# bb-psu-mk-1_1.net
KiCad netlist of a schematic drawn in EAGLE
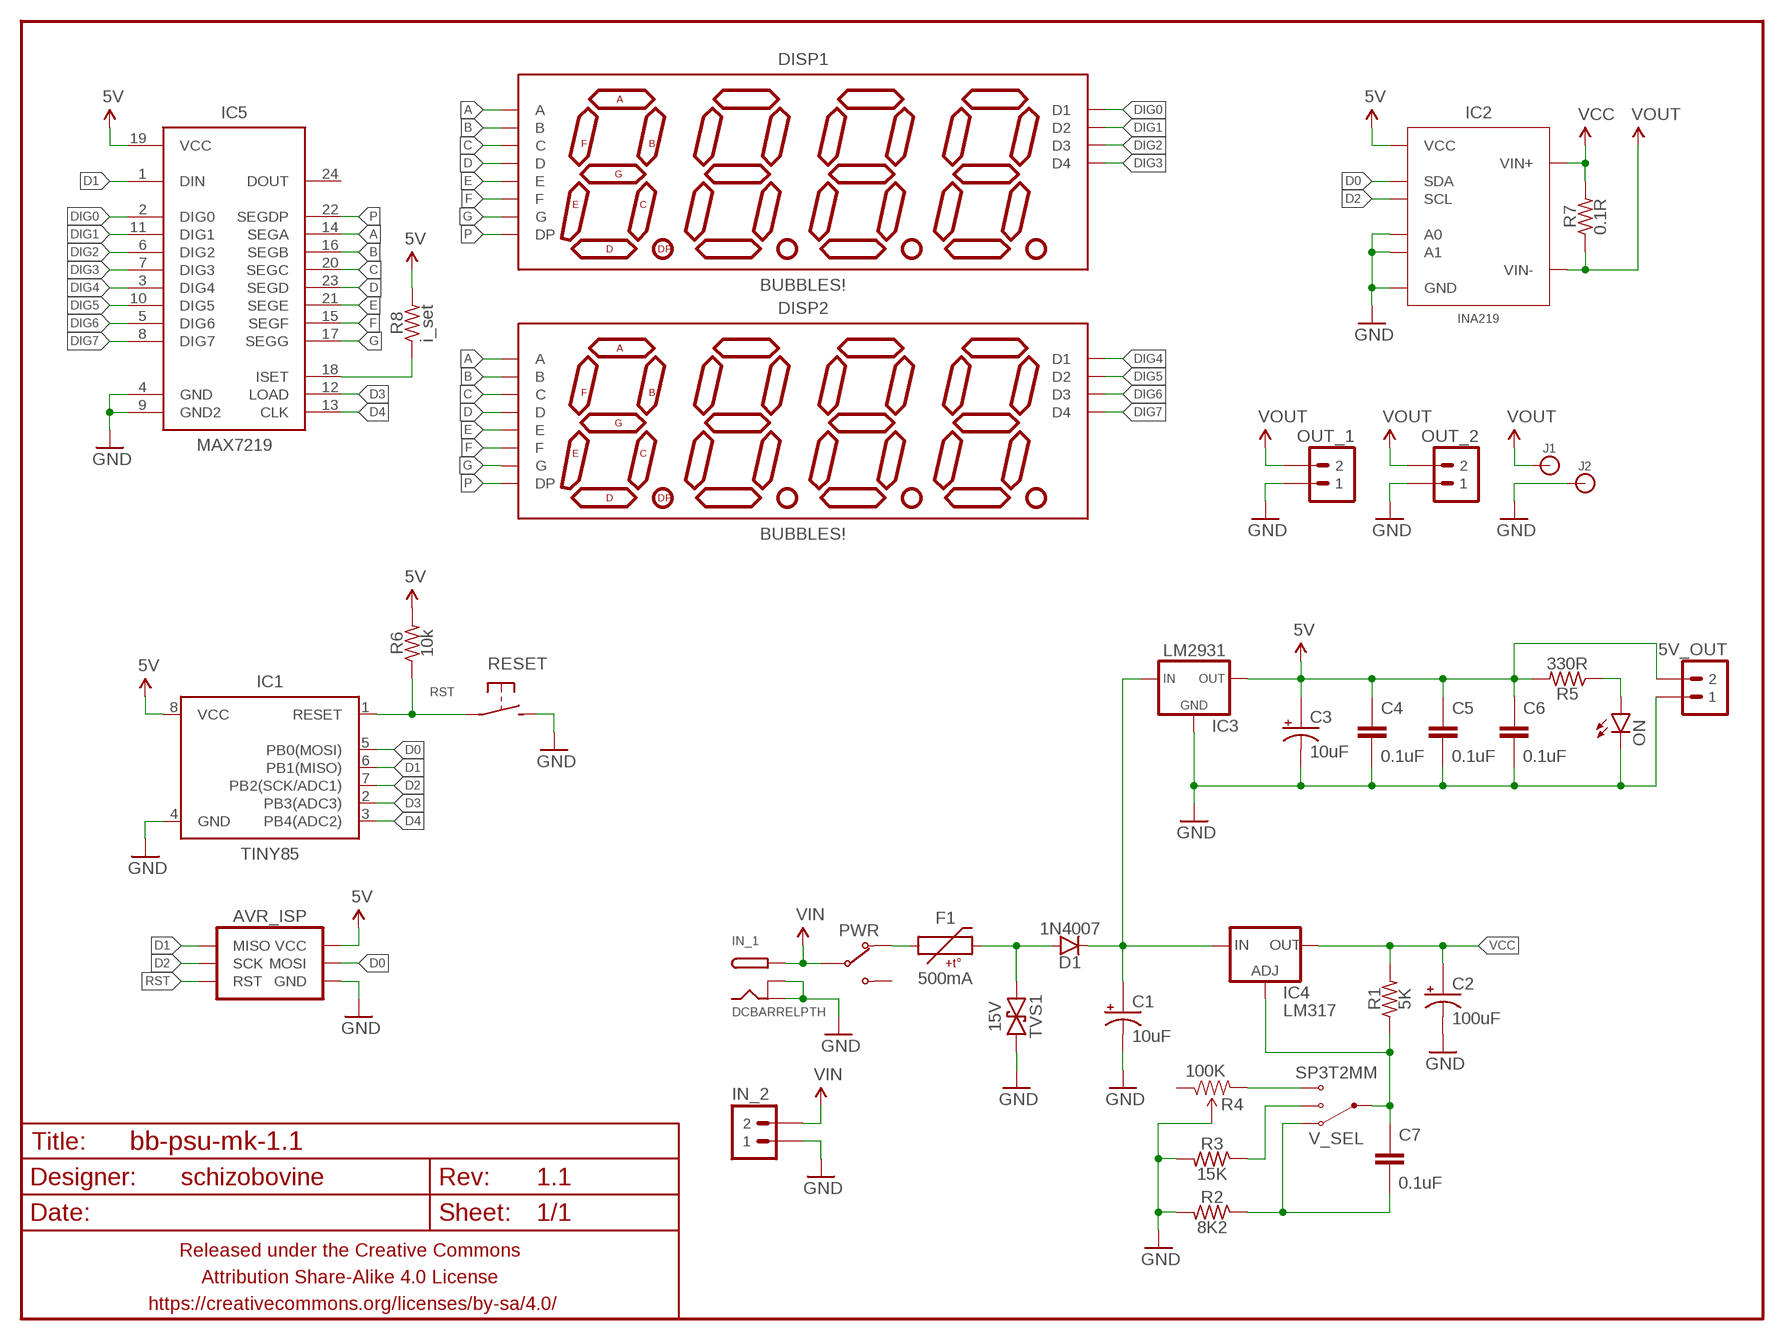
[diagram p0: schematic, sheet 1]

(export (version "E")
  (design (tool "Eeschema 10.0.6"))
  (components
    (comp (ref "5V_OUT")
      (value "M02PTH-CENTERED-R+")
      (footprint "eagle-import:1X02-CENTER-R+")
      (libsource (lib "eagle-import") (part "M02PTH-CENTERED-R+"))
    )
    (comp (ref "AVR_ISP")
      (value "AVR_SPI_PRG_6PTH")
      (footprint "eagle-import:2X3")
      (libsource (lib "eagle-import") (part "AVR_SPI_PRG_6PTH"))
    )
    (comp (ref "C1")
      (value "10uF")
      (footprint "eagle-import:E2,5-6")
      (libsource (lib "eagle-import") (part "CAPACITOR-POLARIZEDE2.5-6"))
    )
    (comp (ref "C2")
      (value "100uF")
      (footprint "eagle-import:E2,5-6")
      (libsource (lib "eagle-import") (part "CAPACITOR-POLARIZEDE2.5-6"))
    )
    (comp (ref "C3")
      (value "10uF")
      (footprint "eagle-import:E2-5")
      (libsource (lib "eagle-import") (part "CAPACITOR-POLARIZEDE2-5"))
    )
    (comp (ref "C4")
      (value "0.1uF")
      (footprint "eagle-import:C025-024X044")
      (libsource (lib "eagle-import") (part "CAPACITOR-CERAMIC025-024X044"))
    )
    (comp (ref "C5")
      (value "0.1uF")
      (footprint "eagle-import:C025-024X044")
      (libsource (lib "eagle-import") (part "CAPACITOR-CERAMIC025-024X044"))
    )
    (comp (ref "C6")
      (value "0.1uF")
      (footprint "eagle-import:C025-024X044")
      (libsource (lib "eagle-import") (part "CAPACITOR-CERAMIC025-024X044"))
    )
    (comp (ref "C7")
      (value "0.1uF")
      (footprint "eagle-import:C025-024X044")
      (libsource (lib "eagle-import") (part "CAPACITOR-CERAMIC025-024X044"))
    )
    (comp (ref "D1")
      (value "1N4007")
      (footprint "eagle-import:DIODE-10.16MM")
      (libsource (lib "eagle-import") (part "DIODEPTH-10.68MM"))
    )
    (comp (ref "DISP1")
      (value "BUBBLES!")
      (footprint "eagle-import:DIL12")
      (libsource (lib "eagle-import") (part "7SEG_4DIGITHP-BUBBLE"))
    )
    (comp (ref "DISP2")
      (value "BUBBLES!")
      (footprint "eagle-import:DIL12")
      (libsource (lib "eagle-import") (part "7SEG_4DIGITHP-BUBBLE"))
    )
    (comp (ref "F1")
      (value "500mA")
      (footprint "eagle-import:PTC-PTH-5.08MM")
      (libsource (lib "eagle-import") (part "PTCPTH-5.08MM"))
    )
    (comp (ref "FRAME1")
      (value "FRAME-LETTERNO_PACKAGE")
      (footprint "eagle-import:DUMMY")
      (fields (field (name "DESIGNER") "schizobovine") (field (name "VERSION") "1.1"))
      (libsource (lib "eagle-import") (part "FRAME-LETTERNO_PACKAGE"))
    )
    (comp (ref "IC1")
      (value "TINY85")
      (footprint "eagle-import:DIP08")
      (libsource (lib "eagle-import") (part "ATTINY45TINY85-20-DIP"))
    )
    (comp (ref "IC2")
      (value "INA219")
      (footprint "eagle-import:SO08")
      (libsource (lib "eagle-import") (part "INA219SOIC8"))
    )
    (comp (ref "IC3")
      (value "LM2931")
      (footprint "eagle-import:TO-92-AMMO")
      (libsource (lib "eagle-import") (part "V_REG_78XXTO-92-INLINE"))
    )
    (comp (ref "IC4")
      (value "LM317")
      (footprint "eagle-import:TO220-THERMPAD")
      (libsource (lib "eagle-import") (part "V_REG_317THERMPAD"))
    )
    (comp (ref "IC5")
      (value "MAX7219")
      (footprint "eagle-import:SO24W")
      (libsource (lib "eagle-import") (part "MAX7219SOIC-W"))
    )
    (comp (ref "IN_1")
      (value "DCBARRELPTH")
      (footprint "eagle-import:DCJACK_2MM_PTH")
      (libsource (lib "eagle-import") (part "DCBARRELPTH"))
    )
    (comp (ref "IN_2")
      (value "M02PTH-CENTERED-R+")
      (footprint "eagle-import:1X02-CENTER-R+")
      (libsource (lib "eagle-import") (part "M02PTH-CENTERED-R+"))
    )
    (comp (ref "J1")
      (value "BANANA_CONNPOAST")
      (footprint "eagle-import:BINDING_POST")
      (libsource (lib "eagle-import") (part "BANANA_CONNPOAST"))
    )
    (comp (ref "J2")
      (value "BANANA_CONNPOAST")
      (footprint "eagle-import:BINDING_POST")
      (libsource (lib "eagle-import") (part "BANANA_CONNPOAST"))
    )
    (comp (ref "ON")
      (value "LED3MM-LESS")
      (footprint "eagle-import:LED3MM-LESSSILK")
      (libsource (lib "eagle-import") (part "LED3MM-LESS"))
    )
    (comp (ref "OUT_1")
      (value "M02PTH-CENTERED-R+")
      (footprint "eagle-import:1X02-CENTER-R+")
      (libsource (lib "eagle-import") (part "M02PTH-CENTERED-R+"))
    )
    (comp (ref "OUT_2")
      (value "M02PTH-CENTERED-R+")
      (footprint "eagle-import:1X02-CENTER-R+")
      (libsource (lib "eagle-import") (part "M02PTH-CENTERED-R+"))
    )
    (comp (ref "PWR")
      (value "SWITCH-SPDTPTH-VERT-2.54MM")
      (footprint "eagle-import:SWITCH-SPDT")
      (libsource (lib "eagle-import") (part "SWITCH-SPDTPTH-VERT-2.54MM"))
    )
    (comp (ref "R1")
      (value "5K")
      (footprint "eagle-import:RESISTOR-AXIAL-PTH-6.35MM")
      (libsource (lib "eagle-import") (part "RESISTORPTH-AXIAL-6.35MM"))
    )
    (comp (ref "R2")
      (value "8K2")
      (footprint "eagle-import:RESISTOR-AXIAL-PTH-6.35MM")
      (libsource (lib "eagle-import") (part "RESISTORPTH-AXIAL-6.35MM"))
    )
    (comp (ref "R3")
      (value "15K")
      (footprint "eagle-import:RESISTOR-AXIAL-PTH-6.35MM")
      (libsource (lib "eagle-import") (part "RESISTORPTH-AXIAL-6.35MM"))
    )
    (comp (ref "R4")
      (value "100K")
      (footprint "eagle-import:3386U")
      (libsource (lib "eagle-import") (part "TRIMPOT-PTH-KNOB"))
    )
    (comp (ref "R5")
      (value "330R")
      (footprint "eagle-import:RESISTOR-AXIAL-PTH-5.08MM")
      (libsource (lib "eagle-import") (part "RESISTORPTH-AXIAL-5.08MM"))
    )
    (comp (ref "R6")
      (value "10k")
      (footprint "eagle-import:RESISTOR-AXIAL-PTH-5.08MM")
      (libsource (lib "eagle-import") (part "RESISTORPTH-AXIAL-5.08MM"))
    )
    (comp (ref "R7")
      (value "0.1R")
      (footprint "eagle-import:RESISTOR-AXIAL-PTH-10.16MM")
      (libsource (lib "eagle-import") (part "RESISTORPTH-AXIAL-10.16MM"))
    )
    (comp (ref "R8")
      (value "i_set")
      (footprint "eagle-import:RESISTOR-AXIAL-PTH-5.08MM")
      (libsource (lib "eagle-import") (part "RESISTORPTH-AXIAL-5.08MM"))
    )
    (comp (ref "RESET")
      (value "SPST-NO-TACT3MM-PTH-SMALL-PADS")
      (footprint "eagle-import:DTS-3-SMALL-PADS")
      (libsource (lib "eagle-import") (part "SPST-NO-TACT3MM-PTH-SMALL-PADS"))
    )
    (comp (ref "TVS1")
      (value "15V")
      (footprint "eagle-import:DO-41-TVS-BI-10.16MM")
      (libsource (lib "eagle-import") (part "TVSDO-41-10.16MM"))
    )
    (comp (ref "V_SEL")
      (value "SP3T2MM")
      (footprint "eagle-import:SP3T-2MM")
      (libsource (lib "eagle-import") (part "SP3T2MM"))
    )
  )
  (nets
    (net (code "1") (name "5V") (class "Default")
      (node (ref "5V_OUT") (pin "2") (pinfunction "2_2") (pintype "passive"))
      (node (ref "AVR_ISP") (pin "2") (pinfunction "VCC_2") (pintype "passive"))
      (node (ref "C3") (pin "+") (pinfunction "+_+") (pintype "passive"))
      (node (ref "C4") (pin "1") (pinfunction "1_1") (pintype "passive"))
      (node (ref "C5") (pin "1") (pinfunction "1_1") (pintype "passive"))
      (node (ref "C6") (pin "1") (pinfunction "1_1") (pintype "passive"))
      (node (ref "IC1") (pin "8") (pinfunction "VCC_8") (pintype "bidirectional"))
      (node (ref "IC2") (pin "5") (pinfunction "VCC_5") (pintype "bidirectional"))
      (node (ref "IC3") (pin "3") (pinfunction "OUT_3") (pintype "bidirectional"))
      (node (ref "IC5") (pin "19") (pinfunction "VCC_19") (pintype "bidirectional"))
      (node (ref "R5") (pin "P$2") (pinfunction "2_P$2") (pintype "passive"))
      (node (ref "R6") (pin "P$2") (pinfunction "2_P$2") (pintype "passive"))
      (node (ref "R8") (pin "P$2") (pinfunction "2_P$2") (pintype "passive"))
    )
    (net (code "2") (name "A") (class "Default")
      (node (ref "DISP1") (pin "12") (pinfunction "A_12") (pintype "bidirectional"))
      (node (ref "DISP2") (pin "12") (pinfunction "A_12") (pintype "bidirectional"))
      (node (ref "IC5") (pin "14") (pinfunction "SEGA_14") (pintype "bidirectional"))
    )
    (net (code "3") (name "B") (class "Default")
      (node (ref "DISP1") (pin "11") (pinfunction "B_11") (pintype "bidirectional"))
      (node (ref "DISP2") (pin "11") (pinfunction "B_11") (pintype "bidirectional"))
      (node (ref "IC5") (pin "16") (pinfunction "SEGB_16") (pintype "bidirectional"))
    )
    (net (code "4") (name "C") (class "Default")
      (node (ref "DISP1") (pin "3") (pinfunction "C_3") (pintype "bidirectional"))
      (node (ref "DISP2") (pin "3") (pinfunction "C_3") (pintype "bidirectional"))
      (node (ref "IC5") (pin "20") (pinfunction "SEGC_20") (pintype "bidirectional"))
    )
    (net (code "5") (name "D") (class "Default")
      (node (ref "DISP1") (pin "8") (pinfunction "D_8") (pintype "bidirectional"))
      (node (ref "DISP2") (pin "8") (pinfunction "D_8") (pintype "bidirectional"))
      (node (ref "IC5") (pin "23") (pinfunction "SEGD_23") (pintype "bidirectional"))
    )
    (net (code "6") (name "D0") (class "Default")
      (node (ref "AVR_ISP") (pin "4") (pinfunction "MOSI_4") (pintype "passive"))
      (node (ref "IC1") (pin "5") (pinfunction "PB0(MOSI)_5") (pintype "bidirectional"))
      (node (ref "IC2") (pin "3") (pinfunction "SDA_3") (pintype "bidirectional"))
    )
    (net (code "7") (name "D1") (class "Default")
      (node (ref "AVR_ISP") (pin "1") (pinfunction "MISO_1") (pintype "passive"))
      (node (ref "IC1") (pin "6") (pinfunction "PB1(MISO)_6") (pintype "bidirectional"))
      (node (ref "IC5") (pin "1") (pinfunction "DIN_1") (pintype "bidirectional"))
    )
    (net (code "8") (name "D2") (class "Default")
      (node (ref "AVR_ISP") (pin "3") (pinfunction "SCK_3") (pintype "passive"))
      (node (ref "IC1") (pin "7") (pinfunction "PB2(SCK/ADC1)_7") (pintype "bidirectional"))
      (node (ref "IC2") (pin "4") (pinfunction "SCL_4") (pintype "bidirectional"))
    )
    (net (code "9") (name "D3") (class "Default")
      (node (ref "IC1") (pin "2") (pinfunction "PB3(ADC3)_2") (pintype "bidirectional"))
      (node (ref "IC5") (pin "12") (pinfunction "LOAD_12") (pintype "bidirectional"))
    )
    (net (code "10") (name "D4") (class "Default")
      (node (ref "IC1") (pin "3") (pinfunction "PB4(ADC2)_3") (pintype "bidirectional"))
      (node (ref "IC5") (pin "13") (pinfunction "CLK_13") (pintype "bidirectional"))
    )
    (net (code "11") (name "DIG0") (class "Default")
      (node (ref "DISP1") (pin "1") (pinfunction "D1_1") (pintype "bidirectional"))
      (node (ref "IC5") (pin "2") (pinfunction "DIG0_2") (pintype "bidirectional"))
    )
    (net (code "12") (name "DIG1") (class "Default")
      (node (ref "DISP1") (pin "10") (pinfunction "D2_10") (pintype "bidirectional"))
      (node (ref "IC5") (pin "11") (pinfunction "DIG1_11") (pintype "bidirectional"))
    )
    (net (code "13") (name "DIG2") (class "Default")
      (node (ref "DISP1") (pin "4") (pinfunction "D3_4") (pintype "bidirectional"))
      (node (ref "IC5") (pin "6") (pinfunction "DIG2_6") (pintype "bidirectional"))
    )
    (net (code "14") (name "DIG3") (class "Default")
      (node (ref "DISP1") (pin "6") (pinfunction "D4_6") (pintype "bidirectional"))
      (node (ref "IC5") (pin "7") (pinfunction "DIG3_7") (pintype "bidirectional"))
    )
    (net (code "15") (name "DIG4") (class "Default")
      (node (ref "DISP2") (pin "1") (pinfunction "D1_1") (pintype "bidirectional"))
      (node (ref "IC5") (pin "3") (pinfunction "DIG4_3") (pintype "bidirectional"))
    )
    (net (code "16") (name "DIG5") (class "Default")
      (node (ref "DISP2") (pin "10") (pinfunction "D2_10") (pintype "bidirectional"))
      (node (ref "IC5") (pin "10") (pinfunction "DIG5_10") (pintype "bidirectional"))
    )
    (net (code "17") (name "DIG6") (class "Default")
      (node (ref "DISP2") (pin "4") (pinfunction "D3_4") (pintype "bidirectional"))
      (node (ref "IC5") (pin "5") (pinfunction "DIG6_5") (pintype "bidirectional"))
    )
    (net (code "18") (name "DIG7") (class "Default")
      (node (ref "DISP2") (pin "6") (pinfunction "D4_6") (pintype "bidirectional"))
      (node (ref "IC5") (pin "8") (pinfunction "DIG7_8") (pintype "bidirectional"))
    )
    (net (code "19") (name "E") (class "Default")
      (node (ref "DISP1") (pin "2") (pinfunction "E_2") (pintype "bidirectional"))
      (node (ref "DISP2") (pin "2") (pinfunction "E_2") (pintype "bidirectional"))
      (node (ref "IC5") (pin "21") (pinfunction "SEGE_21") (pintype "bidirectional"))
    )
    (net (code "20") (name "F") (class "Default")
      (node (ref "DISP1") (pin "9") (pinfunction "F_9") (pintype "bidirectional"))
      (node (ref "DISP2") (pin "9") (pinfunction "F_9") (pintype "bidirectional"))
      (node (ref "IC5") (pin "15") (pinfunction "SEGF_15") (pintype "bidirectional"))
    )
    (net (code "21") (name "G") (class "Default")
      (node (ref "DISP1") (pin "7") (pinfunction "G_7") (pintype "bidirectional"))
      (node (ref "DISP2") (pin "7") (pinfunction "G_7") (pintype "bidirectional"))
      (node (ref "IC5") (pin "17") (pinfunction "SEGG_17") (pintype "bidirectional"))
    )
    (net (code "22") (name "GND") (class "Default")
      (node (ref "5V_OUT") (pin "1") (pinfunction "1_1") (pintype "passive"))
      (node (ref "AVR_ISP") (pin "6") (pinfunction "GND_6") (pintype "passive"))
      (node (ref "C1") (pin "-") (pinfunction "-_-") (pintype "passive"))
      (node (ref "C2") (pin "-") (pinfunction "-_-") (pintype "passive"))
      (node (ref "C3") (pin "-") (pinfunction "-_-") (pintype "passive"))
      (node (ref "C4") (pin "2") (pinfunction "2_2") (pintype "passive"))
      (node (ref "C5") (pin "2") (pinfunction "2_2") (pintype "passive"))
      (node (ref "C6") (pin "2") (pinfunction "2_2") (pintype "passive"))
      (node (ref "IC1") (pin "4") (pinfunction "GND_4") (pintype "bidirectional"))
      (node (ref "IC2") (pin "1") (pinfunction "A1_1") (pintype "bidirectional"))
      (node (ref "IC2") (pin "2") (pinfunction "A0_2") (pintype "bidirectional"))
      (node (ref "IC2") (pin "6") (pinfunction "GND_6") (pintype "bidirectional"))
      (node (ref "IC3") (pin "2") (pinfunction "GND_2") (pintype "bidirectional"))
      (node (ref "IC5") (pin "4") (pinfunction "GND_4") (pintype "bidirectional"))
      (node (ref "IC5") (pin "9") (pinfunction "GND2_9") (pintype "bidirectional"))
      (node (ref "IN_1") (pin "BRK") (pinfunction "BRK_BRK") (pintype "bidirectional"))
      (node (ref "IN_1") (pin "GND") (pinfunction "GND_GND") (pintype "bidirectional"))
      (node (ref "IN_2") (pin "1") (pinfunction "1_1") (pintype "passive"))
      (node (ref "J2") (pin "P$1") (pinfunction "1_P$1") (pintype "passive"))
      (node (ref "ON") (pin "K") (pinfunction "C_K") (pintype "passive"))
      (node (ref "OUT_1") (pin "1") (pinfunction "1_1") (pintype "passive"))
      (node (ref "OUT_2") (pin "1") (pinfunction "1_1") (pintype "passive"))
      (node (ref "R2") (pin "P$2") (pinfunction "2_P$2") (pintype "passive"))
      (node (ref "R3") (pin "P$2") (pinfunction "2_P$2") (pintype "passive"))
      (node (ref "R4") (pin "2") (pinfunction "WIPER_2") (pintype "passive"))
      (node (ref "RESET") (pin "2") (pinfunction "2_2") (pintype "passive"))
      (node (ref "TVS1") (pin "P$2") (pinfunction "2_P$2") (pintype "passive"))
    )
    (net (code "23") (name "Net-(F1-1)") (class "Default")
      (node (ref "F1") (pin "P$1") (pinfunction "1_P$1") (pintype "passive"))
      (node (ref "PWR") (pin "1") (pinfunction "NC_1") (pintype "passive"))
    )
    (net (code "24") (name "Net-(F1-2)") (class "Default")
      (node (ref "D1") (pin "A") (pinfunction "A_A") (pintype "passive"))
      (node (ref "F1") (pin "P$2") (pinfunction "2_P$2") (pintype "passive"))
      (node (ref "TVS1") (pin "P$1") (pinfunction "1_P$1") (pintype "passive"))
    )
    (net (code "25") (name "Net-(IC3-IN)") (class "Default")
      (node (ref "C1") (pin "+") (pinfunction "+_+") (pintype "passive"))
      (node (ref "D1") (pin "C") (pinfunction "C_C") (pintype "passive"))
      (node (ref "IC3") (pin "1") (pinfunction "IN_1") (pintype "bidirectional"))
      (node (ref "IC4") (pin "3") (pinfunction "IN_3") (pintype "input"))
    )
    (net (code "26") (name "Net-(IC4-ADJ)") (class "Default")
      (node (ref "C7") (pin "1") (pinfunction "1_1") (pintype "passive"))
      (node (ref "IC4") (pin "1") (pinfunction "ADJ_1") (pintype "input"))
      (node (ref "R1") (pin "P$1") (pinfunction "1_P$1") (pintype "passive"))
      (node (ref "V_SEL") (pin "P$1") (pinfunction "COM_P$1") (pintype "bidirectional"))
    )
    (net (code "27") (name "Net-(IC5-ISET)") (class "Default")
      (node (ref "IC5") (pin "18") (pinfunction "ISET_18") (pintype "bidirectional"))
      (node (ref "R8") (pin "P$1") (pinfunction "1_P$1") (pintype "passive"))
    )
    (net (code "28") (name "Net-(R2-1)") (class "Default")
      (node (ref "C7") (pin "2") (pinfunction "2_2") (pintype "passive"))
      (node (ref "R2") (pin "P$1") (pinfunction "1_P$1") (pintype "passive"))
      (node (ref "V_SEL") (pin "P$2") (pinfunction "A_P$2") (pintype "bidirectional"))
    )
    (net (code "29") (name "Net-(R3-1)") (class "Default")
      (node (ref "R3") (pin "P$1") (pinfunction "1_P$1") (pintype "passive"))
      (node (ref "V_SEL") (pin "P$3") (pinfunction "B_P$3") (pintype "bidirectional"))
    )
    (net (code "30") (name "Net-(R4-CW)") (class "Default")
      (node (ref "R4") (pin "3") (pinfunction "CW_3") (pintype "passive"))
      (node (ref "V_SEL") (pin "P$4") (pinfunction "C_P$4") (pintype "bidirectional"))
    )
    (net (code "31") (name "Net-(R5-1)") (class "Default")
      (node (ref "ON") (pin "A") (pinfunction "A_A") (pintype "passive"))
      (node (ref "R5") (pin "P$1") (pinfunction "1_P$1") (pintype "passive"))
    )
    (net (code "32") (name "P") (class "Default")
      (node (ref "DISP1") (pin "5") (pinfunction "DP_5") (pintype "bidirectional"))
      (node (ref "DISP2") (pin "5") (pinfunction "DP_5") (pintype "bidirectional"))
      (node (ref "IC5") (pin "22") (pinfunction "SEGDP_22") (pintype "bidirectional"))
    )
    (net (code "33") (name "RST") (class "Default")
      (node (ref "AVR_ISP") (pin "5") (pinfunction "RST_5") (pintype "passive"))
      (node (ref "IC1") (pin "1") (pinfunction "RESET_1") (pintype "bidirectional"))
      (node (ref "R6") (pin "P$1") (pinfunction "1_P$1") (pintype "passive"))
      (node (ref "RESET") (pin "1") (pinfunction "1_1") (pintype "passive"))
    )
    (net (code "34") (name "VCC") (class "Default")
      (node (ref "C2") (pin "+") (pinfunction "+_+") (pintype "passive"))
      (node (ref "IC2") (pin "8") (pinfunction "VIN+_8") (pintype "bidirectional"))
      (node (ref "IC4") (pin "2@1") (pinfunction "OUT_2@1") (pintype "output"))
      (node (ref "IC4") (pin "2@2") (pinfunction "OUT_2@2") (pintype "output"))
      (node (ref "R1") (pin "P$2") (pinfunction "2_P$2") (pintype "passive"))
      (node (ref "R7") (pin "P$2") (pinfunction "2_P$2") (pintype "passive"))
    )
    (net (code "35") (name "VIN") (class "Default")
      (node (ref "IN_1") (pin "PWR") (pinfunction "PWR_PWR") (pintype "bidirectional"))
      (node (ref "IN_2") (pin "2") (pinfunction "2_2") (pintype "passive"))
      (node (ref "PWR") (pin "2") (pinfunction "COM_2") (pintype "passive"))
    )
    (net (code "36") (name "VOUT") (class "Default")
      (node (ref "IC2") (pin "7") (pinfunction "VIN-_7") (pintype "bidirectional"))
      (node (ref "J1") (pin "P$1") (pinfunction "1_P$1") (pintype "passive"))
      (node (ref "OUT_1") (pin "2") (pinfunction "2_2") (pintype "passive"))
      (node (ref "OUT_2") (pin "2") (pinfunction "2_2") (pintype "passive"))
      (node (ref "R7") (pin "P$1") (pinfunction "1_P$1") (pintype "passive"))
    )
    (net (code "37") (name "unconnected-(IC5-DOUT-Pad24)") (class "Default")
      (node (ref "IC5") (pin "24") (pinfunction "DOUT_24") (pintype "bidirectional"))
    )
    (net (code "38") (name "unconnected-(PWR-NO-Pad3)") (class "Default")
      (node (ref "PWR") (pin "3") (pinfunction "NO_3") (pintype "passive"))
    )
    (net (code "39") (name "unconnected-(R4-CCW-Pad1)") (class "Default")
      (node (ref "R4") (pin "1") (pinfunction "CCW_1") (pintype "passive"))
    )
  )
)
